# design.net
KiCad netlist of a schematic drawn in Altium Designer
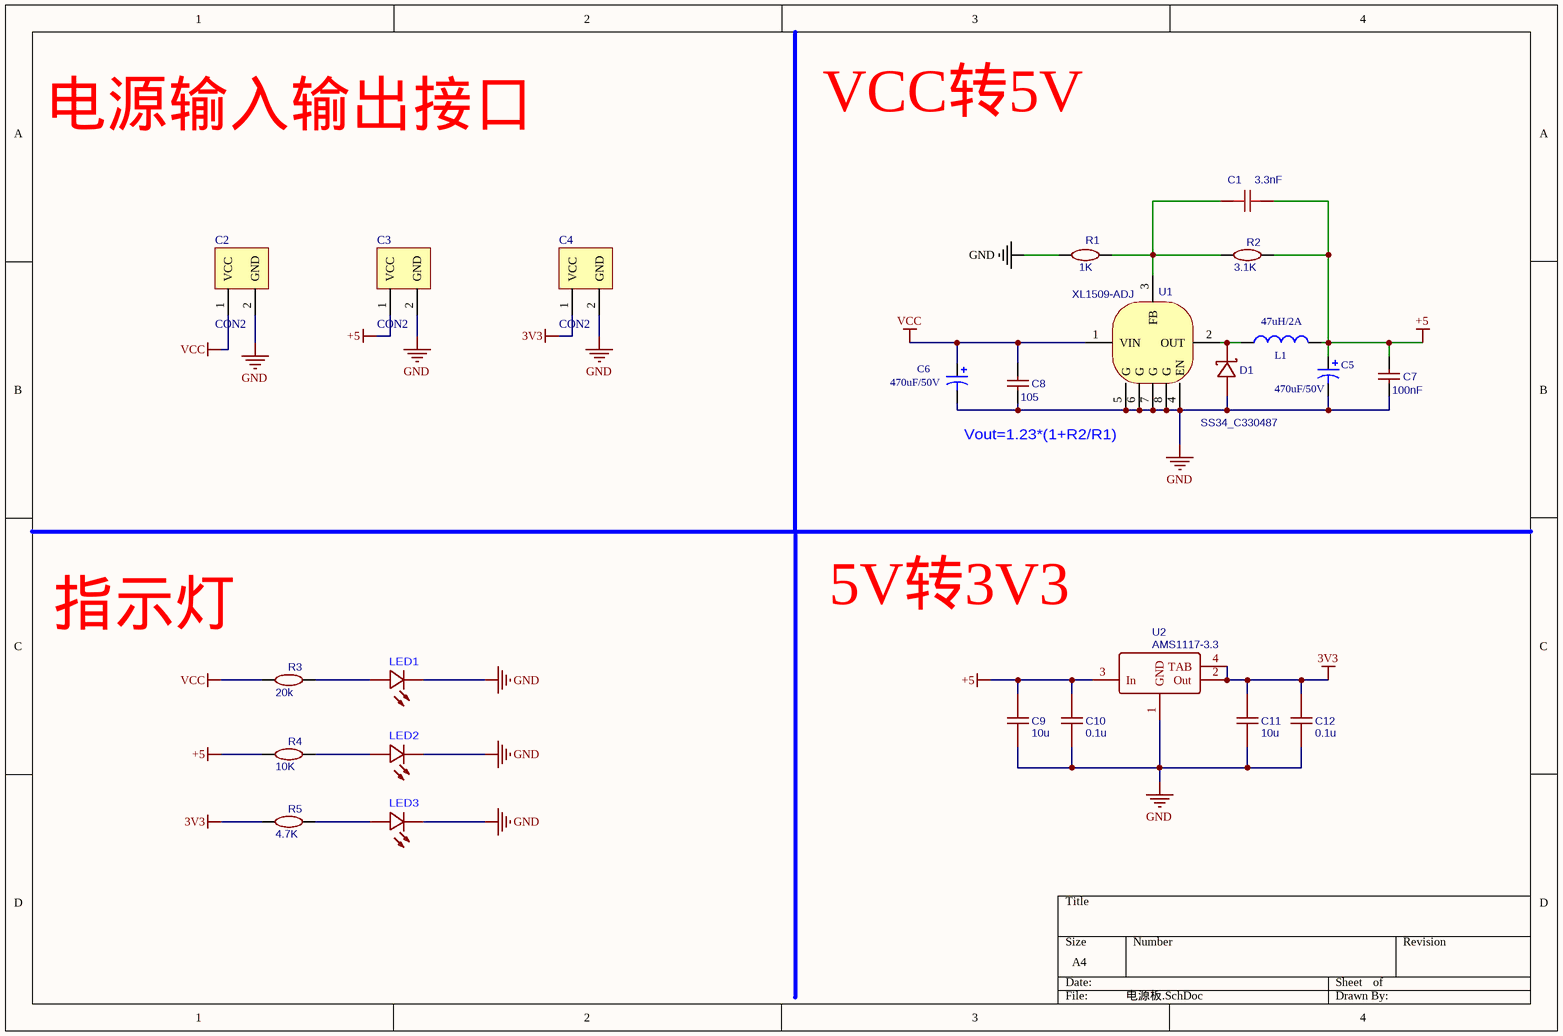
[diagram p0: 电源板.SchDoc]

(export (version "E")
  (design (tool "Eeschema 10.0.6"))
  (components
    (comp (ref "C1")
      (value "3.3nF")
      (footprint "C0603")
      (fields
        (field (name "BOM_SUPPLIER PART") "C190576")
        (field (name "BOM_MANUFACTURER PART") "0603CG332J500NT")
        (field (name "CONTRIBUTOR") "LCSC")
      )
      (libsource (lib "altium-import") (part "root_0_3.3nF_"))
    )
    (comp (ref "C2")
      (value "CON2")
      (footprint "CONN-TH_2P-P3.96_3961S-2P")
      (libsource (lib "电源板") (part "CON2"))
    )
    (comp (ref "C3")
      (value "CON2")
      (footprint "CONN-TH_2P-P3.96_3961S-2P")
      (libsource (lib "电源板") (part "CON2"))
    )
    (comp (ref "C4")
      (value "CON2")
      (footprint "CONN-TH_2P-P3.96_3961S-2P")
      (libsource (lib "电源板") (part "CON2"))
    )
    (comp (ref "C5")
      (value "470uF/50V")
      (footprint "CAP-SMD_BD12.5-L13.0-W13.0-LS13.7-FD")
      (fields (field (name "PUBLISHER") "Altium Limited"))
      (libsource (lib "altium-import") (part "root_3_470uF/35V_"))
    )
    (comp (ref "C6")
      (value "470uF/50V")
      (footprint "CAP-SMD_BD12.5-L13.0-W13.0-LS13.7-FD")
      (fields (field (name "PUBLISHER") "Altium Limited"))
      (libsource (lib "altium-import") (part "root_3_470uF/35V_"))
    )
    (comp (ref "C7")
      (value "100nF")
      (footprint "C0603")
      (fields
        (field (name "BOM_MANUFACTURER PART") "0603B104K160")
        (field (name "BOM_SUPPLIER PART") "C80516")
      )
      (libsource (lib "altium-import") (part "root_1_100nF_"))
    )
    (comp (ref "C8")
      (value "105")
      (footprint "C0603")
      (fields
        (field (name "BOM_MANUFACTURER PART") "0603B104K160")
        (field (name "BOM_SUPPLIER PART") "C80516")
      )
      (libsource (lib "altium-import") (part "root_1_100nF_"))
    )
    (comp (ref "C9")
      (value "10u")
      (footprint "C0603")
      (fields (field (name "CONTRIBUTOR") "LCEDA_Lib"))
      (libsource (lib "altium-import") (part "root_1_10u_"))
    )
    (comp (ref "C10")
      (value "0.1u")
      (footprint "C0603")
      (fields (field (name "CONTRIBUTOR") "LCEDA_Lib"))
      (libsource (lib "altium-import") (part "root_1_0.1u_"))
    )
    (comp (ref "C11")
      (value "10u")
      (footprint "C0603")
      (fields (field (name "CONTRIBUTOR") "LCEDA_Lib"))
      (libsource (lib "altium-import") (part "root_1_10u_"))
    )
    (comp (ref "C12")
      (value "0.1u")
      (footprint "C0603")
      (fields (field (name "CONTRIBUTOR") "LCEDA_Lib"))
      (libsource (lib "altium-import") (part "root_1_0.1u_"))
    )
    (comp (ref "D1")
      (value "SS34_C330487")
      (footprint "SMB_L4.6-W3.6-LS5.3-RD")
      (fields
        (field (name "BOM_SUPPLIER PART") "C330487")
        (field (name "BOM_MANUFACTURER PART") "SS34")
        (field (name "CONTRIBUTOR") "LCSC")
      )
      (libsource (lib "altium-import") (part "root_3_SS34_C330487_"))
    )
    (comp (ref "L1")
      (value "47uH/2A")
      (footprint "IND-SMD_L7.1-W6.6")
      (fields (field (name "PUBLISHER") "Altium Limited"))
      (libsource (lib "altium-import") (part "root_0_47uH/2A_"))
    )
    (comp (ref "LED1")
      (value "~")
      (footprint "LED0603-RD")
      (libsource (lib "altium-import") (part "root_2_TJ-S1608CY6T5ALC6B-A5_"))
    )
    (comp (ref "LED2")
      (value "~")
      (footprint "LED0603-RD")
      (libsource (lib "altium-import") (part "root_2_TJ-S1608CY6T5ALC6B-A5_"))
    )
    (comp (ref "LED3")
      (value "~")
      (footprint "LED0603-RD")
      (libsource (lib "altium-import") (part "root_2_TJ-S1608CY6T5ALC6B-A5_"))
    )
    (comp (ref "R1")
      (value "1K")
      (footprint "0603")
      (fields
        (field (name "BOM_MANUFACTURER PART") "RC0603FR-071KL")
        (field (name "BOM_SUPPLIER PART") "C22548")
      )
      (libsource (lib "altium-import") (part "root_0_1K_"))
    )
    (comp (ref "R2")
      (value "3.1K")
      (footprint "0603")
      (fields
        (field (name "BOM_MANUFACTURER PART") "RC0603FR-071KL")
        (field (name "BOM_SUPPLIER PART") "C22548")
      )
      (libsource (lib "altium-import") (part "root_0_3.1K_"))
    )
    (comp (ref "R3")
      (value "20k")
      (footprint "0603")
      (fields
        (field (name "BOM_MANUFACTURER PART") "RC0603FR-071KL")
        (field (name "BOM_SUPPLIER PART") "C22548")
      )
      (libsource (lib "altium-import") (part "root_0_3.1K_"))
    )
    (comp (ref "R4")
      (value "10K")
      (footprint "0603")
      (fields
        (field (name "BOM_MANUFACTURER PART") "RC0603FR-071KL")
        (field (name "BOM_SUPPLIER PART") "C22548")
      )
      (libsource (lib "altium-import") (part "root_0_3.1K_"))
    )
    (comp (ref "R5")
      (value "4.7K")
      (footprint "0603")
      (fields
        (field (name "BOM_MANUFACTURER PART") "RC0603FR-071KL")
        (field (name "BOM_SUPPLIER PART") "C22548")
      )
      (libsource (lib "altium-import") (part "root_0_3.1K_"))
    )
    (comp (ref "U1")
      (value "XL1509-ADJ")
      (footprint "SOP8")
      (fields (field (name "CONTRIBUTOR") "XYCWJ"))
      (libsource (lib "altium-import") (part "root_0_XL1509-ADJ_"))
    )
    (comp (ref "U2")
      (value "AMS1117-3.3")
      (footprint "SOT-223_L6.5-W3.5-P2.30-LS7.0-BR")
      (fields (field (name "BOM_SUPPLIER PART") "C6186") (field (name "CONTRIBUTOR") "haohan123"))
      (libsource (lib "altium-import") (part "root_0_AMS1117-3.3_"))
    )
  )
  (nets
    (net (code "1") (name "+5") (class "Default")
      (node (ref "C1") (pin "2") (pinfunction "2_2") (pintype "passive"))
      (node (ref "C10") (pin "2") (pinfunction "2_2") (pintype "passive"))
      (node (ref "C3") (pin "1") (pinfunction "VCC_1") (pintype "passive"))
      (node (ref "C5") (pin "1") (pinfunction "1_1") (pintype "passive"))
      (node (ref "C7") (pin "2") (pinfunction "2_2") (pintype "passive"))
      (node (ref "C9") (pin "2") (pinfunction "2_2") (pintype "passive"))
      (node (ref "L1") (pin "2") (pinfunction "2_2") (pintype "passive"))
      (node (ref "R2") (pin "2") (pinfunction "2_2") (pintype "passive"))
      (node (ref "R4") (pin "1") (pinfunction "1_1") (pintype "passive"))
      (node (ref "U2") (pin "3") (pinfunction "In_3") (pintype "passive"))
    )
    (net (code "2") (name "3V3") (class "Default")
      (node (ref "C11") (pin "2") (pinfunction "2_2") (pintype "passive"))
      (node (ref "C12") (pin "2") (pinfunction "2_2") (pintype "passive"))
      (node (ref "C4") (pin "1") (pinfunction "VCC_1") (pintype "passive"))
      (node (ref "R5") (pin "1") (pinfunction "1_1") (pintype "passive"))
      (node (ref "U2") (pin "2") (pinfunction "Out_2") (pintype "passive"))
      (node (ref "U2") (pin "4") (pinfunction "TAB_4") (pintype "passive"))
    )
    (net (code "3") (name "GND") (class "Default")
      (node (ref "C10") (pin "1") (pinfunction "1_1") (pintype "passive"))
      (node (ref "C11") (pin "1") (pinfunction "1_1") (pintype "passive"))
      (node (ref "C12") (pin "1") (pinfunction "1_1") (pintype "passive"))
      (node (ref "C2") (pin "2") (pinfunction "GND_2") (pintype "passive"))
      (node (ref "C3") (pin "2") (pinfunction "GND_2") (pintype "passive"))
      (node (ref "C4") (pin "2") (pinfunction "GND_2") (pintype "passive"))
      (node (ref "C5") (pin "2") (pinfunction "2_2") (pintype "passive"))
      (node (ref "C6") (pin "2") (pinfunction "2_2") (pintype "passive"))
      (node (ref "C7") (pin "1") (pinfunction "1_1") (pintype "passive"))
      (node (ref "C8") (pin "1") (pinfunction "1_1") (pintype "passive"))
      (node (ref "C9") (pin "1") (pinfunction "1_1") (pintype "passive"))
      (node (ref "D1") (pin "2") (pinfunction "A_2") (pintype "passive"))
      (node (ref "LED1") (pin "1") (pinfunction "-_1") (pintype "passive"))
      (node (ref "LED2") (pin "1") (pinfunction "-_1") (pintype "passive"))
      (node (ref "LED3") (pin "1") (pinfunction "-_1") (pintype "passive"))
      (node (ref "R1") (pin "1") (pinfunction "1_1") (pintype "passive"))
      (node (ref "U1") (pin "4") (pinfunction "EN_4") (pintype "passive"))
      (node (ref "U1") (pin "5") (pinfunction "G_5") (pintype "passive"))
      (node (ref "U1") (pin "6") (pinfunction "G_6") (pintype "passive"))
      (node (ref "U1") (pin "7") (pinfunction "G_7") (pintype "passive"))
      (node (ref "U1") (pin "8") (pinfunction "G_8") (pintype "passive"))
      (node (ref "U2") (pin "1") (pinfunction "GND_1") (pintype "passive"))
    )
    (net (code "4") (name "Net-(D1-K)") (class "Default")
      (node (ref "D1") (pin "1") (pinfunction "K_1") (pintype "passive"))
      (node (ref "L1") (pin "1") (pinfunction "1_1") (pintype "passive"))
      (node (ref "U1") (pin "2") (pinfunction "OUT_2") (pintype "passive"))
    )
    (net (code "5") (name "Net-(LED1-+)") (class "Default")
      (node (ref "LED1") (pin "2") (pinfunction "+_2") (pintype "passive"))
      (node (ref "R3") (pin "2") (pinfunction "2_2") (pintype "passive"))
    )
    (net (code "6") (name "Net-(LED2-+)") (class "Default")
      (node (ref "LED2") (pin "2") (pinfunction "+_2") (pintype "passive"))
      (node (ref "R4") (pin "2") (pinfunction "2_2") (pintype "passive"))
    )
    (net (code "7") (name "Net-(LED3-+)") (class "Default")
      (node (ref "LED3") (pin "2") (pinfunction "+_2") (pintype "passive"))
      (node (ref "R5") (pin "2") (pinfunction "2_2") (pintype "passive"))
    )
    (net (code "8") (name "Net-(U1-FB)") (class "Default")
      (node (ref "C1") (pin "1") (pinfunction "1_1") (pintype "passive"))
      (node (ref "R1") (pin "2") (pinfunction "2_2") (pintype "passive"))
      (node (ref "R2") (pin "1") (pinfunction "1_1") (pintype "passive"))
      (node (ref "U1") (pin "3") (pinfunction "FB_3") (pintype "passive"))
    )
    (net (code "9") (name "VCC") (class "Default")
      (node (ref "C2") (pin "1") (pinfunction "VCC_1") (pintype "passive"))
      (node (ref "C6") (pin "1") (pinfunction "1_1") (pintype "passive"))
      (node (ref "C8") (pin "2") (pinfunction "2_2") (pintype "passive"))
      (node (ref "R3") (pin "1") (pinfunction "1_1") (pintype "passive"))
      (node (ref "U1") (pin "1") (pinfunction "VIN_1") (pintype "passive"))
    )
  )
)
